# SH7_-_LOAD_MONITORING_2.net
KiCad netlist of a schematic drawn in Altium Designer
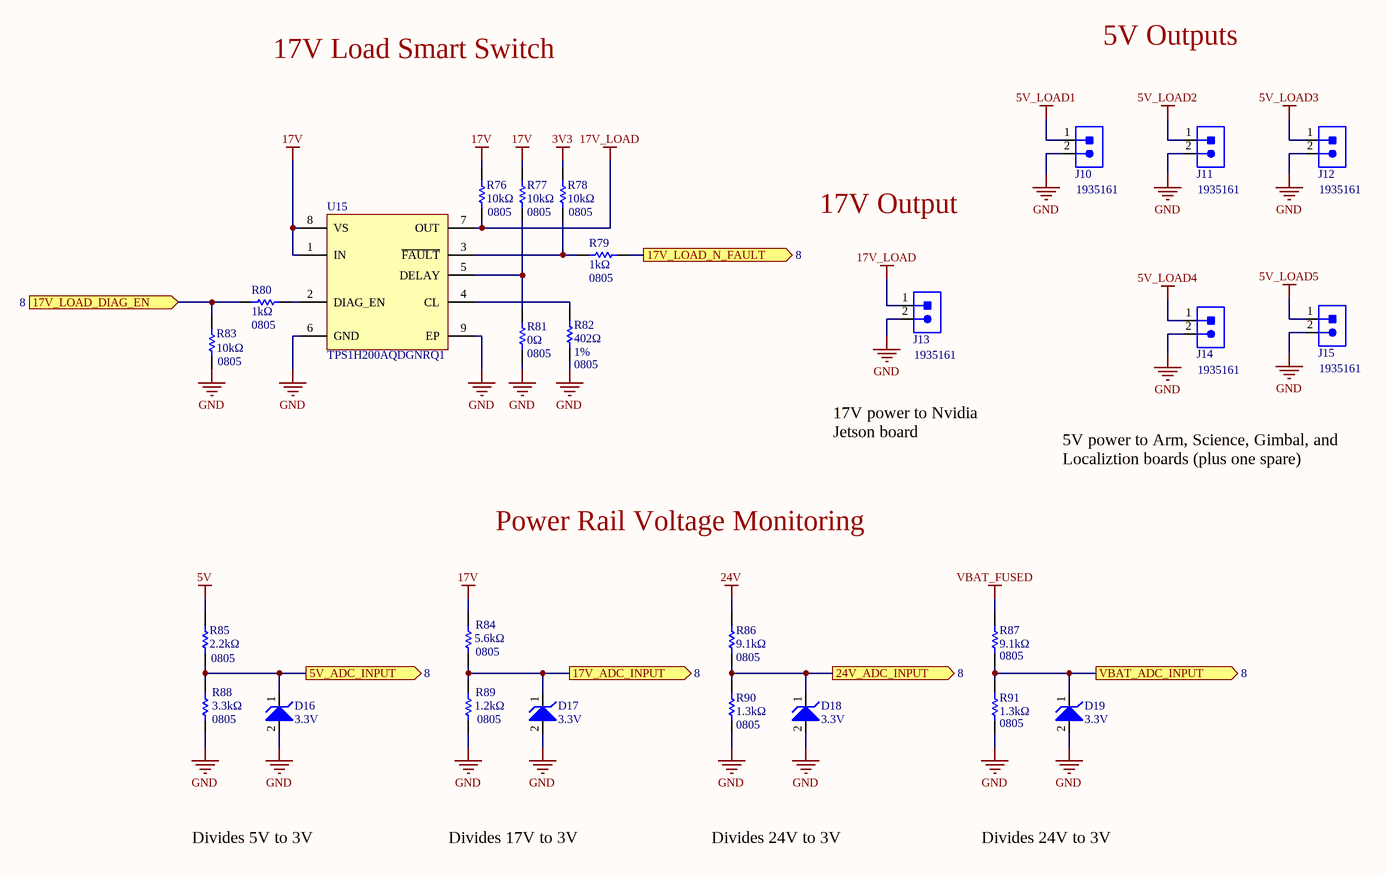
[diagram p0: SH7 - LOAD MONITORING 2.SchDoc]

(export (version "E")
  (design (tool "Eeschema 10.0.6"))
  (components
    (comp (ref "D16")
      (value "TVS_DIODE_UNIDIR_3.3V")
      (footprint "SOD523")
      (description "TVS DIODE 3.3V 14.1V SOD523")
      (fields (field (name "REVERSE STANDOFF VOLTAGE") "3.3V") (field (name "LCSC PART #") "C61148"))
      (libsource (lib "UWRT_Schematic_Library_2020") (part "TVS_DIODE_UNIDIR_3.3V"))
    )
    (comp (ref "D17")
      (value "TVS_DIODE_UNIDIR_3.3V")
      (footprint "SOD523")
      (description "TVS DIODE 3.3V 14.1V SOD523")
      (fields (field (name "REVERSE STANDOFF VOLTAGE") "3.3V") (field (name "LCSC PART #") "C61148"))
      (libsource (lib "UWRT_Schematic_Library_2020") (part "TVS_DIODE_UNIDIR_3.3V"))
    )
    (comp (ref "D18")
      (value "TVS_DIODE_UNIDIR_3.3V")
      (footprint "SOD523")
      (description "TVS DIODE 3.3V 14.1V SOD523")
      (fields (field (name "REVERSE STANDOFF VOLTAGE") "3.3V") (field (name "LCSC PART #") "C61148"))
      (libsource (lib "UWRT_Schematic_Library_2020") (part "TVS_DIODE_UNIDIR_3.3V"))
    )
    (comp (ref "D19")
      (value "TVS_DIODE_UNIDIR_3.3V")
      (footprint "SOD523")
      (description "TVS DIODE 3.3V 14.1V SOD523")
      (fields (field (name "REVERSE STANDOFF VOLTAGE") "3.3V") (field (name "LCSC PART #") "C61148"))
      (libsource (lib "UWRT_Schematic_Library_2020") (part "TVS_DIODE_UNIDIR_3.3V"))
    )
    (comp (ref "J10")
      (value "CON_2M_TERM")
      (footprint "1935161")
      (description "TERM BLK 2POS SIDE ENTRY 5MM")
      (fields (field (name "VOLTAGE") "300V") (field (name "MANUFACTURER PART NUMBER 1") "1935161"))
      (libsource (lib "UWRT_Schematic_Library_2020") (part "CON_2M_TERM"))
    )
    (comp (ref "J11")
      (value "CON_2M_TERM")
      (footprint "1935161")
      (description "TERM BLK 2POS SIDE ENTRY 5MM")
      (fields (field (name "VOLTAGE") "300V") (field (name "MANUFACTURER PART NUMBER 1") "1935161"))
      (libsource (lib "UWRT_Schematic_Library_2020") (part "CON_2M_TERM"))
    )
    (comp (ref "J12")
      (value "CON_2M_TERM")
      (footprint "1935161")
      (description "TERM BLK 2POS SIDE ENTRY 5MM")
      (fields (field (name "VOLTAGE") "300V") (field (name "MANUFACTURER PART NUMBER 1") "1935161"))
      (libsource (lib "UWRT_Schematic_Library_2020") (part "CON_2M_TERM"))
    )
    (comp (ref "J13")
      (value "CON_2M_TERM")
      (footprint "1935161")
      (description "TERM BLK 2POS SIDE ENTRY 5MM")
      (fields (field (name "VOLTAGE") "300V") (field (name "MANUFACTURER PART NUMBER 1") "1935161"))
      (libsource (lib "UWRT_Schematic_Library_2020") (part "CON_2M_TERM"))
    )
    (comp (ref "J14")
      (value "CON_2M_TERM")
      (footprint "1935161")
      (description "TERM BLK 2POS SIDE ENTRY 5MM")
      (fields (field (name "VOLTAGE") "300V") (field (name "MANUFACTURER PART NUMBER 1") "1935161"))
      (libsource (lib "UWRT_Schematic_Library_2020") (part "CON_2M_TERM"))
    )
    (comp (ref "J15")
      (value "CON_2M_TERM")
      (footprint "1935161")
      (description "TERM BLK 2POS SIDE ENTRY 5MM")
      (fields (field (name "VOLTAGE") "300V") (field (name "MANUFACTURER PART NUMBER 1") "1935161"))
      (libsource (lib "UWRT_Schematic_Library_2020") (part "CON_2M_TERM"))
    )
    (comp (ref "R76")
      (value "10kΩ")
      (footprint "RESC0805")
      (description "RES 10K OHM 5% 1/8W 0805")
      (fields
        (field (name "LCSC PART #") "C17414")
        (field (name "PACKAGE/FOOTPRINT") "0805")
        (field (name "Comment") "RES_10kΩ_0805_5%")
      )
      (libsource (lib "UWRT_Schematic_Library_2020") (part "RES_10kΩ_0805_5%"))
    )
    (comp (ref "R77")
      (value "10kΩ")
      (footprint "RESC0805")
      (description "RES 10K OHM 5% 1/8W 0805")
      (fields
        (field (name "LCSC PART #") "C17414")
        (field (name "PACKAGE/FOOTPRINT") "0805")
        (field (name "Comment") "RES_10kΩ_0805_5%")
      )
      (libsource (lib "UWRT_Schematic_Library_2020") (part "RES_10kΩ_0805_5%"))
    )
    (comp (ref "R78")
      (value "10kΩ")
      (footprint "RESC0805")
      (description "RES 10K OHM 5% 1/8W 0805")
      (fields
        (field (name "LCSC PART #") "C17414")
        (field (name "PACKAGE/FOOTPRINT") "0805")
        (field (name "Comment") "RES_10kΩ_0805_5%")
      )
      (libsource (lib "UWRT_Schematic_Library_2020") (part "RES_10kΩ_0805_5%"))
    )
    (comp (ref "R79")
      (value "RES_1kΩ_0805_1%")
      (footprint "RESC0805")
      (description "RES 1K OHM 1% 1/8W 0805")
      (fields
        (field (name "TOLERANCE") "1%")
        (field (name "RESISTANCE") "1kΩ")
        (field (name "LCSC PART #") "C17513")
        (field (name "PACKAGE/FOOTPRINT") "0805")
      )
      (libsource (lib "UWRT_Schematic_Library_2020") (part "RES_1kΩ_0805_1%"))
    )
    (comp (ref "R80")
      (value "RES_1kΩ_0805_1%")
      (footprint "RESC0805")
      (description "RES 1K OHM 1% 1/8W 0805")
      (fields
        (field (name "TOLERANCE") "1%")
        (field (name "RESISTANCE") "1kΩ")
        (field (name "LCSC PART #") "C17513")
        (field (name "PACKAGE/FOOTPRINT") "0805")
      )
      (libsource (lib "UWRT_Schematic_Library_2020") (part "RES_1kΩ_0805_1%"))
    )
    (comp (ref "R81")
      (value "0Ω")
      (footprint "RESC0805")
      (description "RES 0 OHM JUMPER 1/8W 0805")
      (fields
        (field (name "LCSC PART #") "C17477")
        (field (name "PACKAGE/FOOTPRINT") "0805")
        (field (name "Comment") "RES_0Ω_0805")
      )
      (libsource (lib "UWRT_Schematic_Library_2020") (part "RES_0Ω_0805"))
    )
    (comp (ref "R82")
      (value "402Ω")
      (footprint "RESC0805")
      (description "RES 402 OHM 1% 1/8W 0805")
      (fields
        (field (name "TOLERANCE") "1%")
        (field (name "LCSC PART #") "C17681")
        (field (name "PACKAGE/FOOTPRINT") "0805")
        (field (name "Comment") "RES_402Ω_0805_1%")
      )
      (libsource (lib "UWRT_Schematic_Library_2020") (part "RES_402Ω_0805_1%"))
    )
    (comp (ref "R83")
      (value "10kΩ")
      (footprint "RESC0805")
      (description "RES 10K OHM 5% 1/8W 0805")
      (fields
        (field (name "LCSC PART #") "C17414")
        (field (name "PACKAGE/FOOTPRINT") "0805")
        (field (name "Comment") "RES_10kΩ_0805_5%")
      )
      (libsource (lib "UWRT_Schematic_Library_2020") (part "RES_10kΩ_0805_5%"))
    )
    (comp (ref "R84")
      (value "5.6kΩ")
      (footprint "RESC0805")
      (description "RES SMD 5.6K OHM 5% 1/8W 0805")
      (fields
        (field (name "TOLERANCE") "5%")
        (field (name "PACKAGE") "0805")
        (field (name "Comment") "RES_5.6kΩ_0805")
      )
      (libsource (lib "UWRT_Schematic_Library_2020") (part "RES_5.6kΩ_0805_5%"))
    )
    (comp (ref "R85")
      (value "2.2kΩ")
      (footprint "RESC0805")
      (description "RES 2.2K OHM 5% 1/8W 0805")
      (fields
        (field (name "TOLERANCE") "5%")
        (field (name "PACKAGE") "0805")
        (field (name "Comment") "RES_2.2kΩ_0805")
      )
      (libsource (lib "UWRT_Schematic_Library_2020") (part "RES_2.2kΩ_0805_5%"))
    )
    (comp (ref "R86")
      (value "9.1kΩ")
      (footprint "RESC0805")
      (description "RES SMD 9.1K OHM 5% 1/8W 0805")
      (fields
        (field (name "TOLERANCE") "5%")
        (field (name "PACKAGE") "0805")
        (field (name "Comment") "RES_9.1kΩ_0805")
      )
      (libsource (lib "UWRT_Schematic_Library_2020") (part "RES_9.1kΩ_0805_5%"))
    )
    (comp (ref "R87")
      (value "9.1kΩ")
      (footprint "RESC0805")
      (description "RES SMD 9.1K OHM 5% 1/8W 0805")
      (fields
        (field (name "TOLERANCE") "5%")
        (field (name "PACKAGE") "0805")
        (field (name "Comment") "RES_9.1kΩ_0805")
      )
      (libsource (lib "UWRT_Schematic_Library_2020") (part "RES_9.1kΩ_0805_5%"))
    )
    (comp (ref "R88")
      (value "RES_3.3kΩ_0805_1%")
      (footprint "RESC0805")
      (description "RES 3.3K OHM 1% 1/8W 0805")
      (fields
        (field (name "TOLERANCE") "1%")
        (field (name "RESISTANCE") "3.3kΩ")
        (field (name "LCSC PART #") "C26010")
        (field (name "PACKAGE/FOOTPRINT") "0805")
      )
      (libsource (lib "UWRT_Schematic_Library_2020") (part "RES_3.3kΩ_0805_1%"))
    )
    (comp (ref "R89")
      (value "1.2kΩ")
      (footprint "RESC0805")
      (description "RES SMD 1.2K OHM 5% 1/8W 0805")
      (fields
        (field (name "TOLERANCE") "5%")
        (field (name "PACKAGE") "0805")
        (field (name "Comment") "RES_1.2kΩ_0805")
      )
      (libsource (lib "UWRT_Schematic_Library_2020") (part "RES_1.2kΩ_0805_5%"))
    )
    (comp (ref "R90")
      (value "1.3kΩ")
      (footprint "RESC0805")
      (description "RES SMD 1.3K OHM 5% 1/8W 0805")
      (fields
        (field (name "TOLERANCE") "5%")
        (field (name "PACKAGE") "0805")
        (field (name "Comment") "RES_1.3kΩ_0805")
      )
      (libsource (lib "UWRT_Schematic_Library_2020") (part "RES_1.3kΩ_0805_5%"))
    )
    (comp (ref "R91")
      (value "1.3kΩ")
      (footprint "RESC0805")
      (description "RES SMD 1.3K OHM 5% 1/8W 0805")
      (fields
        (field (name "TOLERANCE") "5%")
        (field (name "PACKAGE") "0805")
        (field (name "Comment") "RES_1.3kΩ_0805")
      )
      (libsource (lib "UWRT_Schematic_Library_2020") (part "RES_1.3kΩ_0805_5%"))
    )
    (comp (ref "U15")
      (value "TPS1H200A-Q1")
      (footprint "DGN0008G")
      (description "IC PWR DRIVER N-CHAN 1:1 8MSOP")
      (fields (field (name "MANUFACTURER PART NUMBER 1") "TPS1H200AQDGNRQ1"))
      (libsource (lib "UWRT_Schematic_Library_2020") (part "TPS1H200A-Q1"))
    )
  )
  (nets
    (net (code "1") (name "/5V_ADC_INPUT") (class "Default")
      (node (ref "D16") (pin "1") (pinfunction "1_1") (pintype "passive"))
      (node (ref "R85") (pin "1") (pinfunction "1_1") (pintype "passive"))
      (node (ref "R88") (pin "2") (pinfunction "2_2") (pintype "passive"))
    )
    (net (code "2") (name "/17V_ADC_INPUT") (class "Default")
      (node (ref "D17") (pin "1") (pinfunction "1_1") (pintype "passive"))
      (node (ref "R84") (pin "1") (pinfunction "1_1") (pintype "passive"))
      (node (ref "R89") (pin "2") (pinfunction "2_2") (pintype "passive"))
    )
    (net (code "3") (name "/17V_LOAD_DIAG_EN") (class "Default")
      (node (ref "R80") (pin "1") (pinfunction "1_1") (pintype "passive"))
      (node (ref "R83") (pin "2") (pinfunction "2_2") (pintype "passive"))
    )
    (net (code "4") (name "/17V_LOAD_N_FAULT") (class "Default")
      (node (ref "R79") (pin "2") (pinfunction "2_2") (pintype "passive"))
    )
    (net (code "5") (name "/24V_ADC_INPUT") (class "Default")
      (node (ref "D18") (pin "1") (pinfunction "1_1") (pintype "passive"))
      (node (ref "R86") (pin "1") (pinfunction "1_1") (pintype "passive"))
      (node (ref "R90") (pin "2") (pinfunction "2_2") (pintype "passive"))
    )
    (net (code "6") (name "/VBAT_ADC_INPUT") (class "Default")
      (node (ref "D19") (pin "1") (pinfunction "1_1") (pintype "passive"))
      (node (ref "R87") (pin "1") (pinfunction "1_1") (pintype "passive"))
      (node (ref "R91") (pin "2") (pinfunction "2_2") (pintype "passive"))
    )
    (net (code "7") (name "3V3") (class "Default")
      (node (ref "R78") (pin "2") (pinfunction "2_2") (pintype "passive"))
    )
    (net (code "8") (name "5V") (class "Default")
      (node (ref "R85") (pin "2") (pinfunction "2_2") (pintype "passive"))
    )
    (net (code "9") (name "5V_LOAD1") (class "Default")
      (node (ref "J10") (pin "1") (pinfunction "1_1") (pintype "passive"))
    )
    (net (code "10") (name "5V_LOAD2") (class "Default")
      (node (ref "J11") (pin "1") (pinfunction "1_1") (pintype "passive"))
    )
    (net (code "11") (name "5V_LOAD3") (class "Default")
      (node (ref "J12") (pin "1") (pinfunction "1_1") (pintype "passive"))
    )
    (net (code "12") (name "5V_LOAD4") (class "Default")
      (node (ref "J14") (pin "1") (pinfunction "1_1") (pintype "passive"))
    )
    (net (code "13") (name "5V_LOAD5") (class "Default")
      (node (ref "J15") (pin "1") (pinfunction "1_1") (pintype "passive"))
    )
    (net (code "14") (name "17V") (class "Default")
      (node (ref "R76") (pin "2") (pinfunction "2_2") (pintype "passive"))
      (node (ref "R77") (pin "2") (pinfunction "2_2") (pintype "passive"))
      (node (ref "R84") (pin "2") (pinfunction "2_2") (pintype "passive"))
      (node (ref "U15") (pin "1") (pinfunction "IN_1") (pintype "passive"))
      (node (ref "U15") (pin "8") (pinfunction "VS_8") (pintype "passive"))
    )
    (net (code "15") (name "17V_LOAD") (class "Default")
      (node (ref "J13") (pin "1") (pinfunction "1_1") (pintype "passive"))
      (node (ref "R76") (pin "1") (pinfunction "1_1") (pintype "passive"))
      (node (ref "U15") (pin "7") (pinfunction "OUT_7") (pintype "passive"))
    )
    (net (code "16") (name "24V") (class "Default")
      (node (ref "R86") (pin "2") (pinfunction "2_2") (pintype "passive"))
    )
    (net (code "17") (name "GND") (class "Default")
      (node (ref "D16") (pin "2") (pinfunction "2_2") (pintype "passive"))
      (node (ref "D17") (pin "2") (pinfunction "2_2") (pintype "passive"))
      (node (ref "D18") (pin "2") (pinfunction "2_2") (pintype "passive"))
      (node (ref "D19") (pin "2") (pinfunction "2_2") (pintype "passive"))
      (node (ref "J10") (pin "2") (pinfunction "2_2") (pintype "passive"))
      (node (ref "J11") (pin "2") (pinfunction "2_2") (pintype "passive"))
      (node (ref "J12") (pin "2") (pinfunction "2_2") (pintype "passive"))
      (node (ref "J13") (pin "2") (pinfunction "2_2") (pintype "passive"))
      (node (ref "J14") (pin "2") (pinfunction "2_2") (pintype "passive"))
      (node (ref "J15") (pin "2") (pinfunction "2_2") (pintype "passive"))
      (node (ref "R81") (pin "1") (pinfunction "1_1") (pintype "passive"))
      (node (ref "R82") (pin "1") (pinfunction "1_1") (pintype "passive"))
      (node (ref "R83") (pin "1") (pinfunction "1_1") (pintype "passive"))
      (node (ref "R88") (pin "1") (pinfunction "1_1") (pintype "passive"))
      (node (ref "R89") (pin "1") (pinfunction "1_1") (pintype "passive"))
      (node (ref "R90") (pin "1") (pinfunction "1_1") (pintype "passive"))
      (node (ref "R91") (pin "1") (pinfunction "1_1") (pintype "passive"))
      (node (ref "U15") (pin "6") (pinfunction "GND_6") (pintype "passive"))
      (node (ref "U15") (pin "9") (pinfunction "EP_9") (pintype "passive"))
    )
    (net (code "18") (name "Net-(U15-CL)") (class "Default")
      (node (ref "R82") (pin "2") (pinfunction "2_2") (pintype "passive"))
      (node (ref "U15") (pin "4") (pinfunction "CL_4") (pintype "passive"))
    )
    (net (code "19") (name "Net-(U15-DELAY)") (class "Default")
      (node (ref "R77") (pin "1") (pinfunction "1_1") (pintype "passive"))
      (node (ref "R81") (pin "2") (pinfunction "2_2") (pintype "passive"))
      (node (ref "U15") (pin "5") (pinfunction "DELAY_5") (pintype "passive"))
    )
    (net (code "20") (name "Net-(U15-DIAG_EN)") (class "Default")
      (node (ref "R80") (pin "2") (pinfunction "2_2") (pintype "passive"))
      (node (ref "U15") (pin "2") (pinfunction "DIAG_EN_2") (pintype "passive"))
    )
    (net (code "21") (name "Net-(U15-~{FAULT})") (class "Default")
      (node (ref "R78") (pin "1") (pinfunction "1_1") (pintype "passive"))
      (node (ref "R79") (pin "1") (pinfunction "1_1") (pintype "passive"))
      (node (ref "U15") (pin "3") (pinfunction "~{FAULT}_3") (pintype "passive"))
    )
    (net (code "22") (name "VBAT_FUSED") (class "Default")
      (node (ref "R87") (pin "2") (pinfunction "2_2") (pintype "passive"))
    )
  )
)
